# OSU_Robotics_Kids_LEDS.net
KiCad netlist of a schematic drawn in Altium Designer
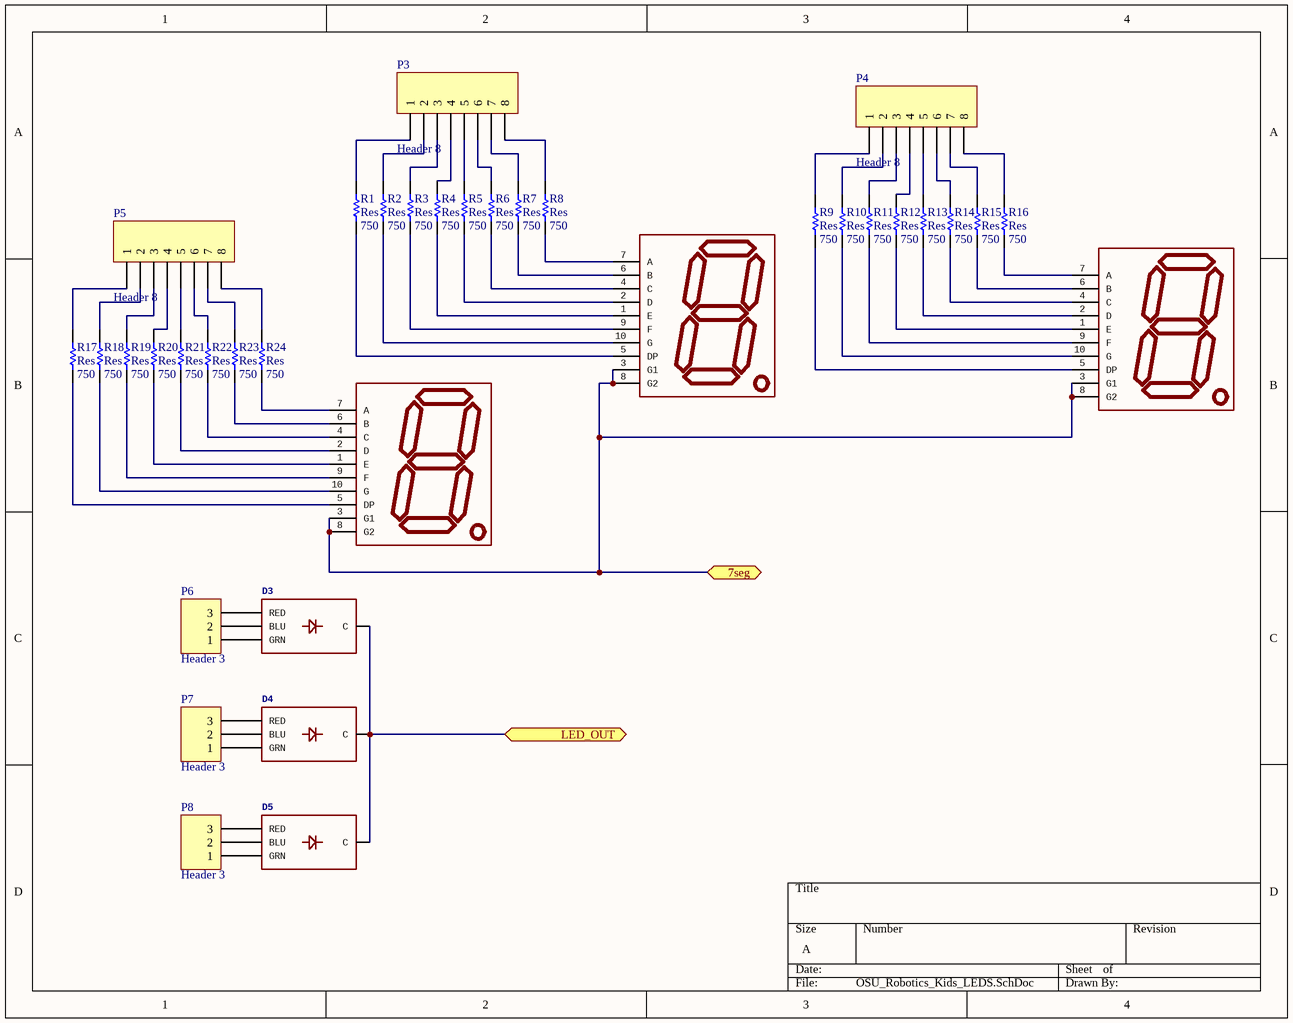
[diagram p0: OSU_Robotics_Kids_LEDS.SchDoc]

(export (version "E")
  (design (tool "Eeschema 10.0.6"))
  (components
    (comp (ref "1")
      (value "7-Segment Display, single digit, 1\"    EZ is for kits. Pads are only exposed on the bottom side to help prevent soldering in upside down.    Datasheet (Red) Datasheet (Blue) SparkFun Products  7-Segment Display - LED (Red) (COM-08546)  7-Segment Display - LED (Blue) (COM-09191)")
      (footprint "7-SEGMENT-1\"PTH")
      (libsource (lib "SparkFun-LED") (part "7-SEGMENT-1DIGIT-1INCH-BLUE"))
    )
    (comp (ref "2")
      (value "7-Segment Display, single digit, 1\"    EZ is for kits. Pads are only exposed on the bottom side to help prevent soldering in upside down.    Datasheet (Red) Datasheet (Blue) SparkFun Products  7-Segment Display - LED (Red) (COM-08546)  7-Segment Display - LED (Blue) (COM-09191)")
      (footprint "7-SEGMENT-1\"PTH")
      (libsource (lib "SparkFun-LED") (part "7-SEGMENT-1DIGIT-1INCH-BLUE"))
    )
    (comp (ref "3")
      (value "7-Segment Display, single digit, 1\"    EZ is for kits. Pads are only exposed on the bottom side to help prevent soldering in upside down.    Datasheet (Red) Datasheet (Blue) SparkFun Products  7-Segment Display - LED (Red) (COM-08546)  7-Segment Display - LED (Blue) (COM-09191)")
      (footprint "7-SEGMENT-1\"PTH")
      (libsource (lib "SparkFun-LED") (part "7-SEGMENT-1DIGIT-1INCH-BLUE"))
    )
    (comp (ref "D3")
      (value "~")
      (footprint "LED-RGB-THRU")
      (libsource (lib "SparkFun-LED") (part "LED-RGB-CCDIFFUSE"))
    )
    (comp (ref "D4")
      (value "~")
      (footprint "LED-RGB-THRU")
      (libsource (lib "SparkFun-LED") (part "LED-RGB-CCDIFFUSE"))
    )
    (comp (ref "D5")
      (value "~")
      (footprint "LED-RGB-THRU")
      (libsource (lib "SparkFun-LED") (part "LED-RGB-CCDIFFUSE"))
    )
    (comp (ref "P3")
      (value "Header 8")
      (footprint "HDR1X8")
      (description "Header, 8-Pin")
      (fields (field (name "PUBLISHER") "Altium Limited"))
      (libsource (lib "Miscellaneous Connectors") (part "Header 8"))
    )
    (comp (ref "P4")
      (value "Header 8")
      (footprint "HDR1X8")
      (description "Header, 8-Pin")
      (fields (field (name "PUBLISHER") "Altium Limited"))
      (libsource (lib "Miscellaneous Connectors") (part "Header 8"))
    )
    (comp (ref "P5")
      (value "Header 8")
      (footprint "HDR1X8")
      (description "Header, 8-Pin")
      (fields (field (name "PUBLISHER") "Altium Limited"))
      (libsource (lib "Miscellaneous Connectors") (part "Header 8"))
    )
    (comp (ref "P6")
      (value "Header 3")
      (footprint "HDR1X3")
      (description "Header, 3-Pin")
      (fields (field (name "PUBLISHER") "Altium Limited"))
      (libsource (lib "Miscellaneous Connectors") (part "Header 3"))
    )
    (comp (ref "P7")
      (value "Header 3")
      (footprint "HDR1X3")
      (description "Header, 3-Pin")
      (fields (field (name "PUBLISHER") "Altium Limited"))
      (libsource (lib "Miscellaneous Connectors") (part "Header 3"))
    )
    (comp (ref "P8")
      (value "Header 3")
      (footprint "HDR1X3")
      (description "Header, 3-Pin")
      (fields (field (name "PUBLISHER") "Altium Limited"))
      (libsource (lib "Miscellaneous Connectors") (part "Header 3"))
    )
    (comp (ref "R1")
      (value "Res")
      (footprint "AXIAL-0.5")
      (description "Semiconductor Resistor")
      (fields (field (name "ALTIUM_VALUE") "750") (field (name "PUBLISHER") "Altium Limited"))
      (libsource (lib "Miscellaneous Devices") (part "Res Semi"))
    )
    (comp (ref "R2")
      (value "Res")
      (footprint "AXIAL-0.5")
      (description "Semiconductor Resistor")
      (fields (field (name "ALTIUM_VALUE") "750") (field (name "PUBLISHER") "Altium Limited"))
      (libsource (lib "Miscellaneous Devices") (part "Res Semi"))
    )
    (comp (ref "R3")
      (value "Res")
      (footprint "AXIAL-0.5")
      (description "Semiconductor Resistor")
      (fields (field (name "ALTIUM_VALUE") "750") (field (name "PUBLISHER") "Altium Limited"))
      (libsource (lib "Miscellaneous Devices") (part "Res Semi"))
    )
    (comp (ref "R4")
      (value "Res")
      (footprint "AXIAL-0.5")
      (description "Semiconductor Resistor")
      (fields (field (name "ALTIUM_VALUE") "750") (field (name "PUBLISHER") "Altium Limited"))
      (libsource (lib "Miscellaneous Devices") (part "Res Semi"))
    )
    (comp (ref "R5")
      (value "Res")
      (footprint "AXIAL-0.5")
      (description "Semiconductor Resistor")
      (fields (field (name "ALTIUM_VALUE") "750") (field (name "PUBLISHER") "Altium Limited"))
      (libsource (lib "Miscellaneous Devices") (part "Res Semi"))
    )
    (comp (ref "R6")
      (value "Res")
      (footprint "AXIAL-0.5")
      (description "Semiconductor Resistor")
      (fields (field (name "ALTIUM_VALUE") "750") (field (name "PUBLISHER") "Altium Limited"))
      (libsource (lib "Miscellaneous Devices") (part "Res Semi"))
    )
    (comp (ref "R7")
      (value "Res")
      (footprint "AXIAL-0.5")
      (description "Semiconductor Resistor")
      (fields (field (name "ALTIUM_VALUE") "750") (field (name "PUBLISHER") "Altium Limited"))
      (libsource (lib "Miscellaneous Devices") (part "Res Semi"))
    )
    (comp (ref "R8")
      (value "Res")
      (footprint "AXIAL-0.5")
      (description "Semiconductor Resistor")
      (fields (field (name "ALTIUM_VALUE") "750") (field (name "PUBLISHER") "Altium Limited"))
      (libsource (lib "Miscellaneous Devices") (part "Res Semi"))
    )
    (comp (ref "R9")
      (value "Res")
      (footprint "AXIAL-0.5")
      (description "Semiconductor Resistor")
      (fields (field (name "ALTIUM_VALUE") "750") (field (name "PUBLISHER") "Altium Limited"))
      (libsource (lib "Miscellaneous Devices") (part "Res Semi"))
    )
    (comp (ref "R10")
      (value "Res")
      (footprint "AXIAL-0.5")
      (description "Semiconductor Resistor")
      (fields (field (name "ALTIUM_VALUE") "750") (field (name "PUBLISHER") "Altium Limited"))
      (libsource (lib "Miscellaneous Devices") (part "Res Semi"))
    )
    (comp (ref "R11")
      (value "Res")
      (footprint "AXIAL-0.5")
      (description "Semiconductor Resistor")
      (fields (field (name "ALTIUM_VALUE") "750") (field (name "PUBLISHER") "Altium Limited"))
      (libsource (lib "Miscellaneous Devices") (part "Res Semi"))
    )
    (comp (ref "R12")
      (value "Res")
      (footprint "AXIAL-0.5")
      (description "Semiconductor Resistor")
      (fields (field (name "ALTIUM_VALUE") "750") (field (name "PUBLISHER") "Altium Limited"))
      (libsource (lib "Miscellaneous Devices") (part "Res Semi"))
    )
    (comp (ref "R13")
      (value "Res")
      (footprint "AXIAL-0.5")
      (description "Semiconductor Resistor")
      (fields (field (name "ALTIUM_VALUE") "750") (field (name "PUBLISHER") "Altium Limited"))
      (libsource (lib "Miscellaneous Devices") (part "Res Semi"))
    )
    (comp (ref "R14")
      (value "Res")
      (footprint "AXIAL-0.5")
      (description "Semiconductor Resistor")
      (fields (field (name "ALTIUM_VALUE") "750") (field (name "PUBLISHER") "Altium Limited"))
      (libsource (lib "Miscellaneous Devices") (part "Res Semi"))
    )
    (comp (ref "R15")
      (value "Res")
      (footprint "AXIAL-0.5")
      (description "Semiconductor Resistor")
      (fields (field (name "ALTIUM_VALUE") "750") (field (name "PUBLISHER") "Altium Limited"))
      (libsource (lib "Miscellaneous Devices") (part "Res Semi"))
    )
    (comp (ref "R16")
      (value "Res")
      (footprint "AXIAL-0.5")
      (description "Semiconductor Resistor")
      (fields (field (name "ALTIUM_VALUE") "750") (field (name "PUBLISHER") "Altium Limited"))
      (libsource (lib "Miscellaneous Devices") (part "Res Semi"))
    )
    (comp (ref "R17")
      (value "Res")
      (footprint "AXIAL-0.5")
      (description "Semiconductor Resistor")
      (fields (field (name "ALTIUM_VALUE") "750") (field (name "PUBLISHER") "Altium Limited"))
      (libsource (lib "Miscellaneous Devices") (part "Res Semi"))
    )
    (comp (ref "R18")
      (value "Res")
      (footprint "AXIAL-0.5")
      (description "Semiconductor Resistor")
      (fields (field (name "ALTIUM_VALUE") "750") (field (name "PUBLISHER") "Altium Limited"))
      (libsource (lib "Miscellaneous Devices") (part "Res Semi"))
    )
    (comp (ref "R19")
      (value "Res")
      (footprint "AXIAL-0.5")
      (description "Semiconductor Resistor")
      (fields (field (name "ALTIUM_VALUE") "750") (field (name "PUBLISHER") "Altium Limited"))
      (libsource (lib "Miscellaneous Devices") (part "Res Semi"))
    )
    (comp (ref "R20")
      (value "Res")
      (footprint "AXIAL-0.5")
      (description "Semiconductor Resistor")
      (fields (field (name "ALTIUM_VALUE") "750") (field (name "PUBLISHER") "Altium Limited"))
      (libsource (lib "Miscellaneous Devices") (part "Res Semi"))
    )
    (comp (ref "R21")
      (value "Res")
      (footprint "AXIAL-0.5")
      (description "Semiconductor Resistor")
      (fields (field (name "ALTIUM_VALUE") "750") (field (name "PUBLISHER") "Altium Limited"))
      (libsource (lib "Miscellaneous Devices") (part "Res Semi"))
    )
    (comp (ref "R22")
      (value "Res")
      (footprint "AXIAL-0.5")
      (description "Semiconductor Resistor")
      (fields (field (name "ALTIUM_VALUE") "750") (field (name "PUBLISHER") "Altium Limited"))
      (libsource (lib "Miscellaneous Devices") (part "Res Semi"))
    )
    (comp (ref "R23")
      (value "Res")
      (footprint "AXIAL-0.5")
      (description "Semiconductor Resistor")
      (fields (field (name "ALTIUM_VALUE") "750") (field (name "PUBLISHER") "Altium Limited"))
      (libsource (lib "Miscellaneous Devices") (part "Res Semi"))
    )
    (comp (ref "R24")
      (value "Res")
      (footprint "AXIAL-0.5")
      (description "Semiconductor Resistor")
      (fields (field (name "ALTIUM_VALUE") "750") (field (name "PUBLISHER") "Altium Limited"))
      (libsource (lib "Miscellaneous Devices") (part "Res Semi"))
    )
  )
  (nets
    (net (code "1") (name "/7seg") (class "Default")
      (node (ref "1") (pin "3") (pinfunction "G1_3") (pintype "passive"))
      (node (ref "1") (pin "8") (pinfunction "G2_8") (pintype "passive"))
      (node (ref "2") (pin "3") (pinfunction "G1_3") (pintype "passive"))
      (node (ref "2") (pin "8") (pinfunction "G2_8") (pintype "passive"))
      (node (ref "3") (pin "3") (pinfunction "G1_3") (pintype "passive"))
      (node (ref "3") (pin "8") (pinfunction "G2_8") (pintype "passive"))
    )
    (net (code "2") (name "/LED_OUT") (class "Default")
      (node (ref "D3") (pin "2") (pinfunction "C_2") (pintype "passive"))
      (node (ref "D4") (pin "2") (pinfunction "C_2") (pintype "passive"))
      (node (ref "D5") (pin "2") (pinfunction "C_2") (pintype "passive"))
    )
    (net (code "3") (name "Net-(1-A)") (class "Default")
      (node (ref "1") (pin "7") (pinfunction "A_7") (pintype "passive"))
      (node (ref "R8") (pin "1") (pinfunction "1_1") (pintype "passive"))
    )
    (net (code "4") (name "Net-(1-B)") (class "Default")
      (node (ref "1") (pin "6") (pinfunction "B_6") (pintype "passive"))
      (node (ref "R7") (pin "1") (pinfunction "1_1") (pintype "passive"))
    )
    (net (code "5") (name "Net-(1-C)") (class "Default")
      (node (ref "1") (pin "4") (pinfunction "C_4") (pintype "passive"))
      (node (ref "R6") (pin "1") (pinfunction "1_1") (pintype "passive"))
    )
    (net (code "6") (name "Net-(1-D)") (class "Default")
      (node (ref "1") (pin "2") (pinfunction "D_2") (pintype "passive"))
      (node (ref "R5") (pin "1") (pinfunction "1_1") (pintype "passive"))
    )
    (net (code "7") (name "Net-(1-DP)") (class "Default")
      (node (ref "1") (pin "5") (pinfunction "DP_5") (pintype "passive"))
      (node (ref "R1") (pin "1") (pinfunction "1_1") (pintype "passive"))
    )
    (net (code "8") (name "Net-(1-E)") (class "Default")
      (node (ref "1") (pin "1") (pinfunction "E_1") (pintype "passive"))
      (node (ref "R4") (pin "1") (pinfunction "1_1") (pintype "passive"))
    )
    (net (code "9") (name "Net-(1-F)") (class "Default")
      (node (ref "1") (pin "9") (pinfunction "F_9") (pintype "passive"))
      (node (ref "R3") (pin "1") (pinfunction "1_1") (pintype "passive"))
    )
    (net (code "10") (name "Net-(1-G)") (class "Default")
      (node (ref "1") (pin "10") (pinfunction "G_10") (pintype "passive"))
      (node (ref "R2") (pin "1") (pinfunction "1_1") (pintype "passive"))
    )
    (net (code "11") (name "Net-(2-A)") (class "Default")
      (node (ref "2") (pin "7") (pinfunction "A_7") (pintype "passive"))
      (node (ref "R16") (pin "1") (pinfunction "1_1") (pintype "passive"))
    )
    (net (code "12") (name "Net-(2-B)") (class "Default")
      (node (ref "2") (pin "6") (pinfunction "B_6") (pintype "passive"))
      (node (ref "R15") (pin "1") (pinfunction "1_1") (pintype "passive"))
    )
    (net (code "13") (name "Net-(2-C)") (class "Default")
      (node (ref "2") (pin "4") (pinfunction "C_4") (pintype "passive"))
      (node (ref "R14") (pin "1") (pinfunction "1_1") (pintype "passive"))
    )
    (net (code "14") (name "Net-(2-D)") (class "Default")
      (node (ref "2") (pin "2") (pinfunction "D_2") (pintype "passive"))
      (node (ref "R13") (pin "1") (pinfunction "1_1") (pintype "passive"))
    )
    (net (code "15") (name "Net-(2-DP)") (class "Default")
      (node (ref "2") (pin "5") (pinfunction "DP_5") (pintype "passive"))
      (node (ref "R9") (pin "1") (pinfunction "1_1") (pintype "passive"))
    )
    (net (code "16") (name "Net-(2-E)") (class "Default")
      (node (ref "2") (pin "1") (pinfunction "E_1") (pintype "passive"))
      (node (ref "R12") (pin "1") (pinfunction "1_1") (pintype "passive"))
    )
    (net (code "17") (name "Net-(2-F)") (class "Default")
      (node (ref "2") (pin "9") (pinfunction "F_9") (pintype "passive"))
      (node (ref "R11") (pin "1") (pinfunction "1_1") (pintype "passive"))
    )
    (net (code "18") (name "Net-(2-G)") (class "Default")
      (node (ref "2") (pin "10") (pinfunction "G_10") (pintype "passive"))
      (node (ref "R10") (pin "1") (pinfunction "1_1") (pintype "passive"))
    )
    (net (code "19") (name "Net-(3-A)") (class "Default")
      (node (ref "3") (pin "7") (pinfunction "A_7") (pintype "passive"))
      (node (ref "R24") (pin "1") (pinfunction "1_1") (pintype "passive"))
    )
    (net (code "20") (name "Net-(3-B)") (class "Default")
      (node (ref "3") (pin "6") (pinfunction "B_6") (pintype "passive"))
      (node (ref "R23") (pin "1") (pinfunction "1_1") (pintype "passive"))
    )
    (net (code "21") (name "Net-(3-C)") (class "Default")
      (node (ref "3") (pin "4") (pinfunction "C_4") (pintype "passive"))
      (node (ref "R22") (pin "1") (pinfunction "1_1") (pintype "passive"))
    )
    (net (code "22") (name "Net-(3-D)") (class "Default")
      (node (ref "3") (pin "2") (pinfunction "D_2") (pintype "passive"))
      (node (ref "R21") (pin "1") (pinfunction "1_1") (pintype "passive"))
    )
    (net (code "23") (name "Net-(3-DP)") (class "Default")
      (node (ref "3") (pin "5") (pinfunction "DP_5") (pintype "passive"))
      (node (ref "R17") (pin "1") (pinfunction "1_1") (pintype "passive"))
    )
    (net (code "24") (name "Net-(3-E)") (class "Default")
      (node (ref "3") (pin "1") (pinfunction "E_1") (pintype "passive"))
      (node (ref "R20") (pin "1") (pinfunction "1_1") (pintype "passive"))
    )
    (net (code "25") (name "Net-(3-F)") (class "Default")
      (node (ref "3") (pin "9") (pinfunction "F_9") (pintype "passive"))
      (node (ref "R19") (pin "1") (pinfunction "1_1") (pintype "passive"))
    )
    (net (code "26") (name "Net-(3-G)") (class "Default")
      (node (ref "3") (pin "10") (pinfunction "G_10") (pintype "passive"))
      (node (ref "R18") (pin "1") (pinfunction "1_1") (pintype "passive"))
    )
    (net (code "27") (name "Net-(D3-BLU)") (class "Default")
      (node (ref "D3") (pin "4") (pinfunction "BLU_4") (pintype "passive"))
      (node (ref "P6") (pin "2") (pinfunction "2_2") (pintype "passive"))
    )
    (net (code "28") (name "Net-(D3-GRN)") (class "Default")
      (node (ref "D3") (pin "3") (pinfunction "GRN_3") (pintype "passive"))
      (node (ref "P6") (pin "1") (pinfunction "1_1") (pintype "passive"))
    )
    (net (code "29") (name "Net-(D3-RED)") (class "Default")
      (node (ref "D3") (pin "1") (pinfunction "RED_1") (pintype "passive"))
      (node (ref "P6") (pin "3") (pinfunction "3_3") (pintype "passive"))
    )
    (net (code "30") (name "Net-(D4-BLU)") (class "Default")
      (node (ref "D4") (pin "4") (pinfunction "BLU_4") (pintype "passive"))
      (node (ref "P7") (pin "2") (pinfunction "2_2") (pintype "passive"))
    )
    (net (code "31") (name "Net-(D4-GRN)") (class "Default")
      (node (ref "D4") (pin "3") (pinfunction "GRN_3") (pintype "passive"))
      (node (ref "P7") (pin "1") (pinfunction "1_1") (pintype "passive"))
    )
    (net (code "32") (name "Net-(D4-RED)") (class "Default")
      (node (ref "D4") (pin "1") (pinfunction "RED_1") (pintype "passive"))
      (node (ref "P7") (pin "3") (pinfunction "3_3") (pintype "passive"))
    )
    (net (code "33") (name "Net-(D5-BLU)") (class "Default")
      (node (ref "D5") (pin "4") (pinfunction "BLU_4") (pintype "passive"))
      (node (ref "P8") (pin "2") (pinfunction "2_2") (pintype "passive"))
    )
    (net (code "34") (name "Net-(D5-GRN)") (class "Default")
      (node (ref "D5") (pin "3") (pinfunction "GRN_3") (pintype "passive"))
      (node (ref "P8") (pin "1") (pinfunction "1_1") (pintype "passive"))
    )
    (net (code "35") (name "Net-(D5-RED)") (class "Default")
      (node (ref "D5") (pin "1") (pinfunction "RED_1") (pintype "passive"))
      (node (ref "P8") (pin "3") (pinfunction "3_3") (pintype "passive"))
    )
    (net (code "36") (name "Net-(P3-Pad1)") (class "Default")
      (node (ref "P3") (pin "1") (pinfunction "1_1") (pintype "passive"))
      (node (ref "R1") (pin "2") (pinfunction "2_2") (pintype "passive"))
    )
    (net (code "37") (name "Net-(P3-Pad2)") (class "Default")
      (node (ref "P3") (pin "2") (pinfunction "2_2") (pintype "passive"))
      (node (ref "R2") (pin "2") (pinfunction "2_2") (pintype "passive"))
    )
    (net (code "38") (name "Net-(P3-Pad3)") (class "Default")
      (node (ref "P3") (pin "3") (pinfunction "3_3") (pintype "passive"))
      (node (ref "R3") (pin "2") (pinfunction "2_2") (pintype "passive"))
    )
    (net (code "39") (name "Net-(P3-Pad4)") (class "Default")
      (node (ref "P3") (pin "4") (pinfunction "4_4") (pintype "passive"))
      (node (ref "R4") (pin "2") (pinfunction "2_2") (pintype "passive"))
    )
    (net (code "40") (name "Net-(P3-Pad5)") (class "Default")
      (node (ref "P3") (pin "5") (pinfunction "5_5") (pintype "passive"))
      (node (ref "R5") (pin "2") (pinfunction "2_2") (pintype "passive"))
    )
    (net (code "41") (name "Net-(P3-Pad6)") (class "Default")
      (node (ref "P3") (pin "6") (pinfunction "6_6") (pintype "passive"))
      (node (ref "R6") (pin "2") (pinfunction "2_2") (pintype "passive"))
    )
    (net (code "42") (name "Net-(P3-Pad7)") (class "Default")
      (node (ref "P3") (pin "7") (pinfunction "7_7") (pintype "passive"))
      (node (ref "R7") (pin "2") (pinfunction "2_2") (pintype "passive"))
    )
    (net (code "43") (name "Net-(P3-Pad8)") (class "Default")
      (node (ref "P3") (pin "8") (pinfunction "8_8") (pintype "passive"))
      (node (ref "R8") (pin "2") (pinfunction "2_2") (pintype "passive"))
    )
    (net (code "44") (name "Net-(P4-Pad1)") (class "Default")
      (node (ref "P4") (pin "1") (pinfunction "1_1") (pintype "passive"))
      (node (ref "R9") (pin "2") (pinfunction "2_2") (pintype "passive"))
    )
    (net (code "45") (name "Net-(P4-Pad2)") (class "Default")
      (node (ref "P4") (pin "2") (pinfunction "2_2") (pintype "passive"))
      (node (ref "R10") (pin "2") (pinfunction "2_2") (pintype "passive"))
    )
    (net (code "46") (name "Net-(P4-Pad3)") (class "Default")
      (node (ref "P4") (pin "3") (pinfunction "3_3") (pintype "passive"))
      (node (ref "R11") (pin "2") (pinfunction "2_2") (pintype "passive"))
    )
    (net (code "47") (name "Net-(P4-Pad4)") (class "Default")
      (node (ref "P4") (pin "4") (pinfunction "4_4") (pintype "passive"))
      (node (ref "R12") (pin "2") (pinfunction "2_2") (pintype "passive"))
    )
    (net (code "48") (name "Net-(P4-Pad5)") (class "Default")
      (node (ref "P4") (pin "5") (pinfunction "5_5") (pintype "passive"))
      (node (ref "R13") (pin "2") (pinfunction "2_2") (pintype "passive"))
    )
    (net (code "49") (name "Net-(P4-Pad6)") (class "Default")
      (node (ref "P4") (pin "6") (pinfunction "6_6") (pintype "passive"))
      (node (ref "R14") (pin "2") (pinfunction "2_2") (pintype "passive"))
    )
    (net (code "50") (name "Net-(P4-Pad7)") (class "Default")
      (node (ref "P4") (pin "7") (pinfunction "7_7") (pintype "passive"))
      (node (ref "R15") (pin "2") (pinfunction "2_2") (pintype "passive"))
    )
    (net (code "51") (name "Net-(P4-Pad8)") (class "Default")
      (node (ref "P4") (pin "8") (pinfunction "8_8") (pintype "passive"))
      (node (ref "R16") (pin "2") (pinfunction "2_2") (pintype "passive"))
    )
    (net (code "52") (name "Net-(P5-Pad1)") (class "Default")
      (node (ref "P5") (pin "1") (pinfunction "1_1") (pintype "passive"))
      (node (ref "R17") (pin "2") (pinfunction "2_2") (pintype "passive"))
    )
    (net (code "53") (name "Net-(P5-Pad2)") (class "Default")
      (node (ref "P5") (pin "2") (pinfunction "2_2") (pintype "passive"))
      (node (ref "R18") (pin "2") (pinfunction "2_2") (pintype "passive"))
    )
    (net (code "54") (name "Net-(P5-Pad3)") (class "Default")
      (node (ref "P5") (pin "3") (pinfunction "3_3") (pintype "passive"))
      (node (ref "R19") (pin "2") (pinfunction "2_2") (pintype "passive"))
    )
    (net (code "55") (name "Net-(P5-Pad4)") (class "Default")
      (node (ref "P5") (pin "4") (pinfunction "4_4") (pintype "passive"))
      (node (ref "R20") (pin "2") (pinfunction "2_2") (pintype "passive"))
    )
    (net (code "56") (name "Net-(P5-Pad5)") (class "Default")
      (node (ref "P5") (pin "5") (pinfunction "5_5") (pintype "passive"))
      (node (ref "R21") (pin "2") (pinfunction "2_2") (pintype "passive"))
    )
    (net (code "57") (name "Net-(P5-Pad6)") (class "Default")
      (node (ref "P5") (pin "6") (pinfunction "6_6") (pintype "passive"))
      (node (ref "R22") (pin "2") (pinfunction "2_2") (pintype "passive"))
    )
    (net (code "58") (name "Net-(P5-Pad7)") (class "Default")
      (node (ref "P5") (pin "7") (pinfunction "7_7") (pintype "passive"))
      (node (ref "R23") (pin "2") (pinfunction "2_2") (pintype "passive"))
    )
    (net (code "59") (name "Net-(P5-Pad8)") (class "Default")
      (node (ref "P5") (pin "8") (pinfunction "8_8") (pintype "passive"))
      (node (ref "R24") (pin "2") (pinfunction "2_2") (pintype "passive"))
    )
  )
)
